# CAN-D_Coat_Rev1.net
KiCad netlist of a schematic drawn in EAGLE
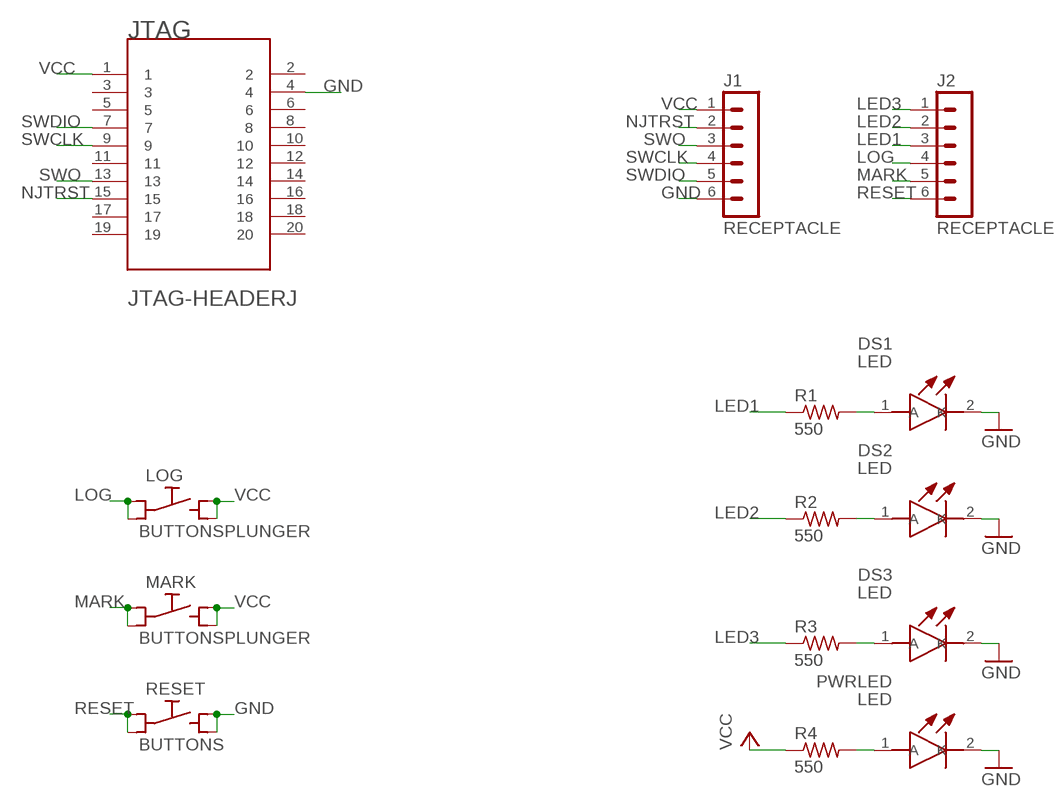
[diagram p0: schematic, sheet 1]

(export (version "E")
  (design (tool "Eeschema 10.0.6"))
  (components
    (comp (ref "DS1")
      (value "LED")
      (footprint "eagle-import:L130-6580001400001")
      (fields
        (field (name "MANUFACTURER_PART_NUMBER") "L130-6580001400001")
        (field (name "MOUSER_PART_NUMBER") "997-L130-65800014001")
        (field (name "RS_PART_NUMBER") "1709867")
      )
      (libsource (lib "eagle-import") (part "LED"))
    )
    (comp (ref "DS2")
      (value "LED")
      (footprint "eagle-import:L130-6580001400001")
      (fields
        (field (name "MANUFACTURER_PART_NUMBER") "L130-6580001400001")
        (field (name "MOUSER_PART_NUMBER") "997-L130-65800014001")
        (field (name "RS_PART_NUMBER") "1709867")
      )
      (libsource (lib "eagle-import") (part "LED"))
    )
    (comp (ref "DS3")
      (value "LED")
      (footprint "eagle-import:L130-6580001400001")
      (fields
        (field (name "MANUFACTURER_PART_NUMBER") "L130-6580001400001")
        (field (name "MOUSER_PART_NUMBER") "997-L130-65800014001")
        (field (name "RS_PART_NUMBER") "1709867")
      )
      (libsource (lib "eagle-import") (part "LED"))
    )
    (comp (ref "J1")
      (value "RECEPTACLE")
      (footprint "eagle-import:SSM-106-L-SV-K-TR")
      (libsource (lib "eagle-import") (part "RECEPTACLE"))
    )
    (comp (ref "J2")
      (value "RECEPTACLE")
      (footprint "eagle-import:SSM-106-L-SV-K-TR")
      (libsource (lib "eagle-import") (part "RECEPTACLE"))
    )
    (comp (ref "JTAG")
      (value "JTAG-HEADERJ")
      (footprint "eagle-import:TSM-110-02-L-DV-A-P-TR")
      (fields
        (field (name "DIGI-KEY_PART_NUMBER") "SAM14887CT-ND")
        (field (name "MF") "Samtec Inc.")
        (field (name "MP") "TSM-110-01-T-DV-TR")
      )
      (libsource (lib "eagle-import") (part "JTAG-HEADERJ"))
    )
    (comp (ref "LOG")
      (value "BUTTONSPLUNGER")
      (footprint "eagle-import:TL3301SPF260QG")
      (libsource (lib "eagle-import") (part "BUTTONSPLUNGER"))
    )
    (comp (ref "MARK")
      (value "BUTTONSPLUNGER")
      (footprint "eagle-import:TL3301SPF260QG")
      (libsource (lib "eagle-import") (part "BUTTONSPLUNGER"))
    )
    (comp (ref "PWRLED")
      (value "LED")
      (footprint "eagle-import:L130-6580001400001")
      (fields
        (field (name "MANUFACTURER_PART_NUMBER") "L130-6580001400001")
        (field (name "MOUSER_PART_NUMBER") "997-L130-65800014001")
        (field (name "RS_PART_NUMBER") "1709867")
      )
      (libsource (lib "eagle-import") (part "LED"))
    )
    (comp (ref "R1")
      (value "550")
      (footprint "eagle-import:R0603")
      (libsource (lib "eagle-import") (part "RESISTOR"))
    )
    (comp (ref "R2")
      (value "550")
      (footprint "eagle-import:R0603")
      (libsource (lib "eagle-import") (part "RESISTOR"))
    )
    (comp (ref "R3")
      (value "550")
      (footprint "eagle-import:R0603")
      (libsource (lib "eagle-import") (part "R-US_R0603"))
    )
    (comp (ref "R4")
      (value "550")
      (footprint "eagle-import:R0603")
      (libsource (lib "eagle-import") (part "RESISTOR"))
    )
    (comp (ref "RESET")
      (value "BUTTONS")
      (footprint "eagle-import:1301.9314")
      (libsource (lib "eagle-import") (part "BUTTONS"))
    )
  )
  (nets
    (net (code "1") (name "/LED1") (class "Default")
      (node (ref "J2") (pin "3") (pinfunction "3_3") (pintype "passive"))
      (node (ref "R1") (pin "1") (pinfunction "1_1") (pintype "passive"))
    )
    (net (code "2") (name "/LED2") (class "Default")
      (node (ref "J2") (pin "2") (pinfunction "2_2") (pintype "passive"))
      (node (ref "R2") (pin "1") (pinfunction "1_1") (pintype "passive"))
    )
    (net (code "3") (name "/LED3") (class "Default")
      (node (ref "J2") (pin "1") (pinfunction "1_1") (pintype "passive"))
      (node (ref "R3") (pin "1") (pinfunction "1_1") (pintype "passive"))
    )
    (net (code "4") (name "/LOG") (class "Default")
      (node (ref "J2") (pin "4") (pinfunction "4_4") (pintype "passive"))
      (node (ref "LOG") (pin "C1") (pinfunction "C_C1") (pintype "passive"))
      (node (ref "LOG") (pin "C2") (pinfunction "C_C2") (pintype "passive"))
    )
    (net (code "5") (name "/MARK") (class "Default")
      (node (ref "J2") (pin "5") (pinfunction "5_5") (pintype "passive"))
      (node (ref "MARK") (pin "C1") (pinfunction "C_C1") (pintype "passive"))
      (node (ref "MARK") (pin "C2") (pinfunction "C_C2") (pintype "passive"))
    )
    (net (code "6") (name "/NJTRST") (class "Default")
      (node (ref "J1") (pin "2") (pinfunction "2_2") (pintype "passive"))
      (node (ref "JTAG") (pin "15") (pinfunction "15_15") (pintype "passive"))
    )
    (net (code "7") (name "/RESET") (class "Default")
      (node (ref "J2") (pin "6") (pinfunction "6_6") (pintype "passive"))
      (node (ref "RESET") (pin "C1") (pinfunction "C_C1") (pintype "passive"))
      (node (ref "RESET") (pin "C2") (pinfunction "C_C2") (pintype "passive"))
    )
    (net (code "8") (name "/SWCLK") (class "Default")
      (node (ref "J1") (pin "4") (pinfunction "4_4") (pintype "passive"))
      (node (ref "JTAG") (pin "9") (pinfunction "9_9") (pintype "passive"))
    )
    (net (code "9") (name "/SWDIO") (class "Default")
      (node (ref "J1") (pin "5") (pinfunction "5_5") (pintype "passive"))
      (node (ref "JTAG") (pin "7") (pinfunction "7_7") (pintype "passive"))
    )
    (net (code "10") (name "/SWO") (class "Default")
      (node (ref "J1") (pin "3") (pinfunction "3_3") (pintype "passive"))
      (node (ref "JTAG") (pin "13") (pinfunction "13_13") (pintype "passive"))
    )
    (net (code "11") (name "GND") (class "Default")
      (node (ref "DS1") (pin "2") (pinfunction "K_2") (pintype "bidirectional"))
      (node (ref "DS2") (pin "2") (pinfunction "K_2") (pintype "bidirectional"))
      (node (ref "DS3") (pin "2") (pinfunction "K_2") (pintype "bidirectional"))
      (node (ref "J1") (pin "6") (pinfunction "6_6") (pintype "passive"))
      (node (ref "JTAG") (pin "4") (pinfunction "4_4") (pintype "passive"))
      (node (ref "PWRLED") (pin "2") (pinfunction "K_2") (pintype "bidirectional"))
      (node (ref "RESET") (pin "NO1") (pinfunction "NO_NO1") (pintype "passive"))
      (node (ref "RESET") (pin "NO2") (pinfunction "NO_NO2") (pintype "passive"))
    )
    (net (code "12") (name "Net-(DS1-A)") (class "Default")
      (node (ref "DS1") (pin "1") (pinfunction "A_1") (pintype "bidirectional"))
      (node (ref "R1") (pin "2") (pinfunction "2_2") (pintype "passive"))
    )
    (net (code "13") (name "Net-(DS2-A)") (class "Default")
      (node (ref "DS2") (pin "1") (pinfunction "A_1") (pintype "bidirectional"))
      (node (ref "R2") (pin "2") (pinfunction "2_2") (pintype "passive"))
    )
    (net (code "14") (name "Net-(DS3-A)") (class "Default")
      (node (ref "DS3") (pin "1") (pinfunction "A_1") (pintype "bidirectional"))
      (node (ref "R3") (pin "2") (pinfunction "2_2") (pintype "passive"))
    )
    (net (code "15") (name "Net-(PWRLED-A)") (class "Default")
      (node (ref "PWRLED") (pin "1") (pinfunction "A_1") (pintype "bidirectional"))
      (node (ref "R4") (pin "2") (pinfunction "2_2") (pintype "passive"))
    )
    (net (code "16") (name "VCC") (class "Default")
      (node (ref "J1") (pin "1") (pinfunction "1_1") (pintype "passive"))
      (node (ref "JTAG") (pin "1") (pinfunction "1_1") (pintype "passive"))
      (node (ref "LOG") (pin "NO1") (pinfunction "NO_NO1") (pintype "passive"))
      (node (ref "LOG") (pin "NO2") (pinfunction "NO_NO2") (pintype "passive"))
      (node (ref "MARK") (pin "NO1") (pinfunction "NO_NO1") (pintype "passive"))
      (node (ref "MARK") (pin "NO2") (pinfunction "NO_NO2") (pintype "passive"))
      (node (ref "R4") (pin "1") (pinfunction "1_1") (pintype "passive"))
    )
    (net (code "17") (name "unconnected-(JTAG-Pad2)") (class "Default")
      (node (ref "JTAG") (pin "2") (pinfunction "2_2") (pintype "passive"))
    )
    (net (code "18") (name "unconnected-(JTAG-Pad3)") (class "Default")
      (node (ref "JTAG") (pin "3") (pinfunction "3_3") (pintype "passive"))
    )
    (net (code "19") (name "unconnected-(JTAG-Pad5)") (class "Default")
      (node (ref "JTAG") (pin "5") (pinfunction "5_5") (pintype "passive"))
    )
    (net (code "20") (name "unconnected-(JTAG-Pad6)") (class "Default")
      (node (ref "JTAG") (pin "6") (pinfunction "6_6") (pintype "passive"))
    )
    (net (code "21") (name "unconnected-(JTAG-Pad8)") (class "Default")
      (node (ref "JTAG") (pin "8") (pinfunction "8_8") (pintype "passive"))
    )
    (net (code "22") (name "unconnected-(JTAG-Pad10)") (class "Default")
      (node (ref "JTAG") (pin "10") (pinfunction "10_10") (pintype "passive"))
    )
    (net (code "23") (name "unconnected-(JTAG-Pad11)") (class "Default")
      (node (ref "JTAG") (pin "11") (pinfunction "11_11") (pintype "passive"))
    )
    (net (code "24") (name "unconnected-(JTAG-Pad12)") (class "Default")
      (node (ref "JTAG") (pin "12") (pinfunction "12_12") (pintype "passive"))
    )
    (net (code "25") (name "unconnected-(JTAG-Pad14)") (class "Default")
      (node (ref "JTAG") (pin "14") (pinfunction "14_14") (pintype "passive"))
    )
    (net (code "26") (name "unconnected-(JTAG-Pad16)") (class "Default")
      (node (ref "JTAG") (pin "16") (pinfunction "16_16") (pintype "passive"))
    )
    (net (code "27") (name "unconnected-(JTAG-Pad17)") (class "Default")
      (node (ref "JTAG") (pin "17") (pinfunction "17_17") (pintype "passive"))
    )
    (net (code "28") (name "unconnected-(JTAG-Pad18)") (class "Default")
      (node (ref "JTAG") (pin "18") (pinfunction "18_18") (pintype "passive"))
    )
    (net (code "29") (name "unconnected-(JTAG-Pad19)") (class "Default")
      (node (ref "JTAG") (pin "19") (pinfunction "19_19") (pintype "passive"))
    )
    (net (code "30") (name "unconnected-(JTAG-Pad20)") (class "Default")
      (node (ref "JTAG") (pin "20") (pinfunction "20_20") (pintype "passive"))
    )
  )
)
